# SCH_nixie_clock_2022-01-09.net
KiCad netlist of a schematic drawn in EasyEDA
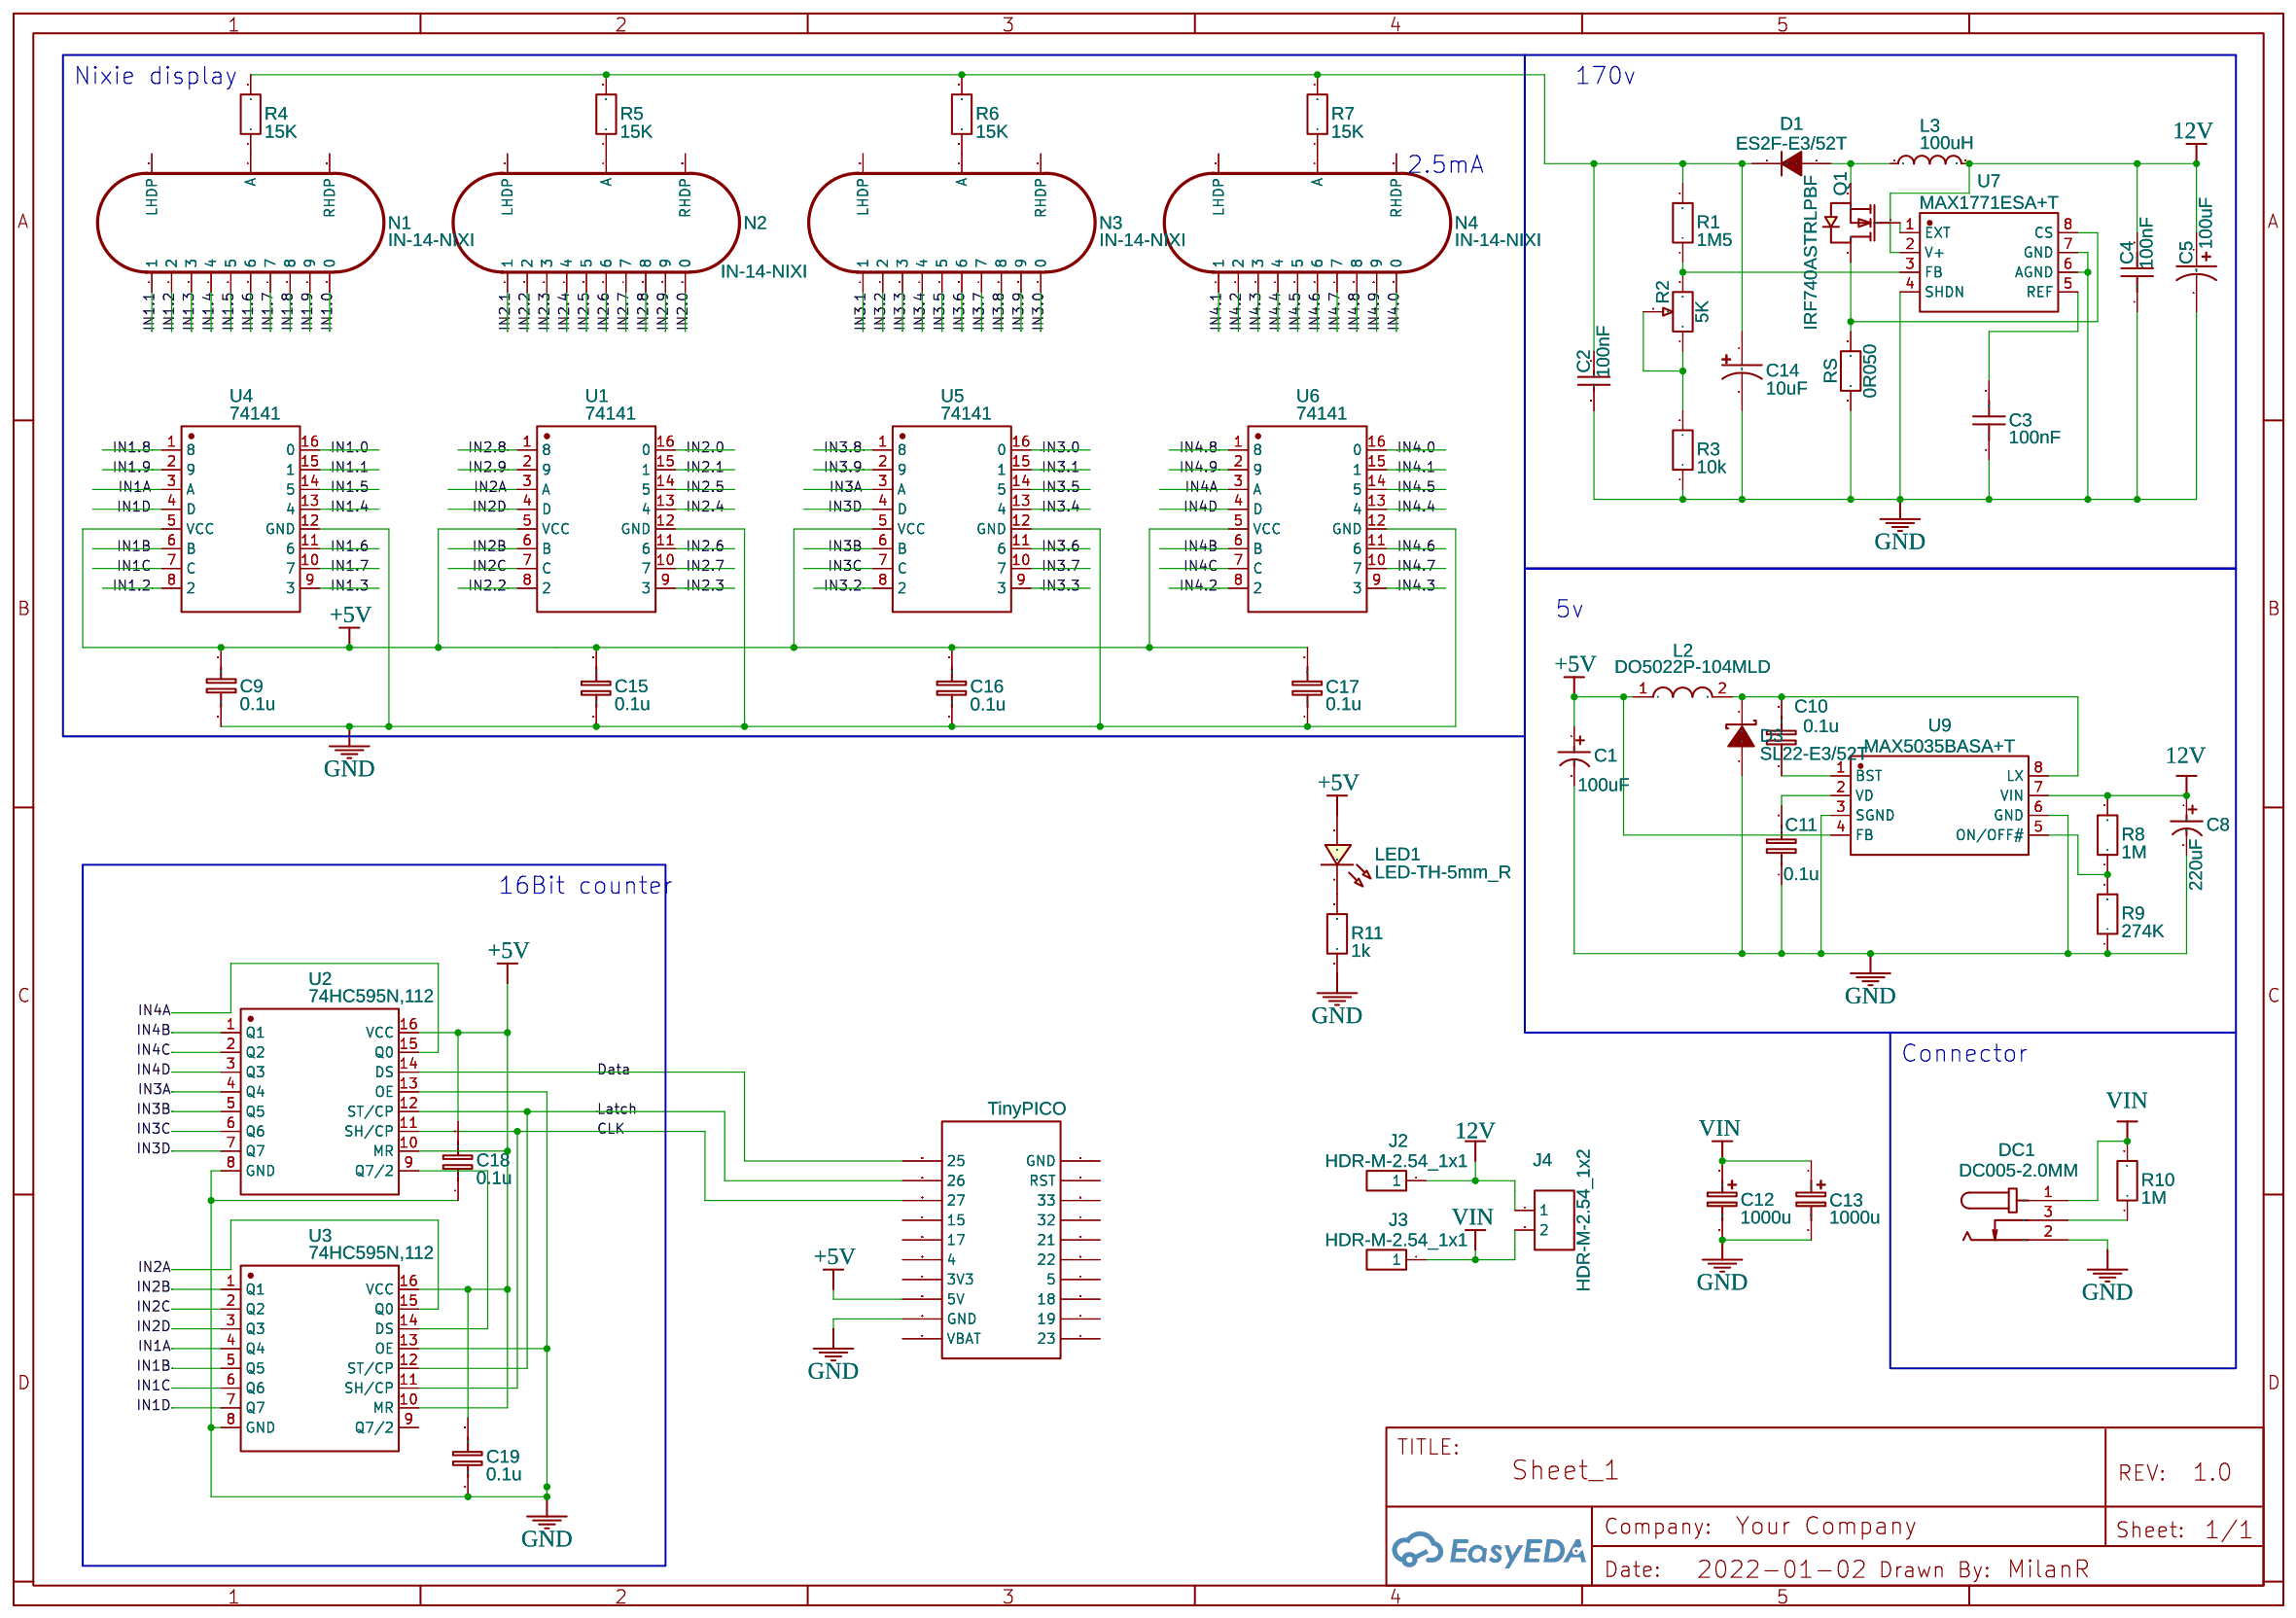
[diagram p0: Sheet_1]
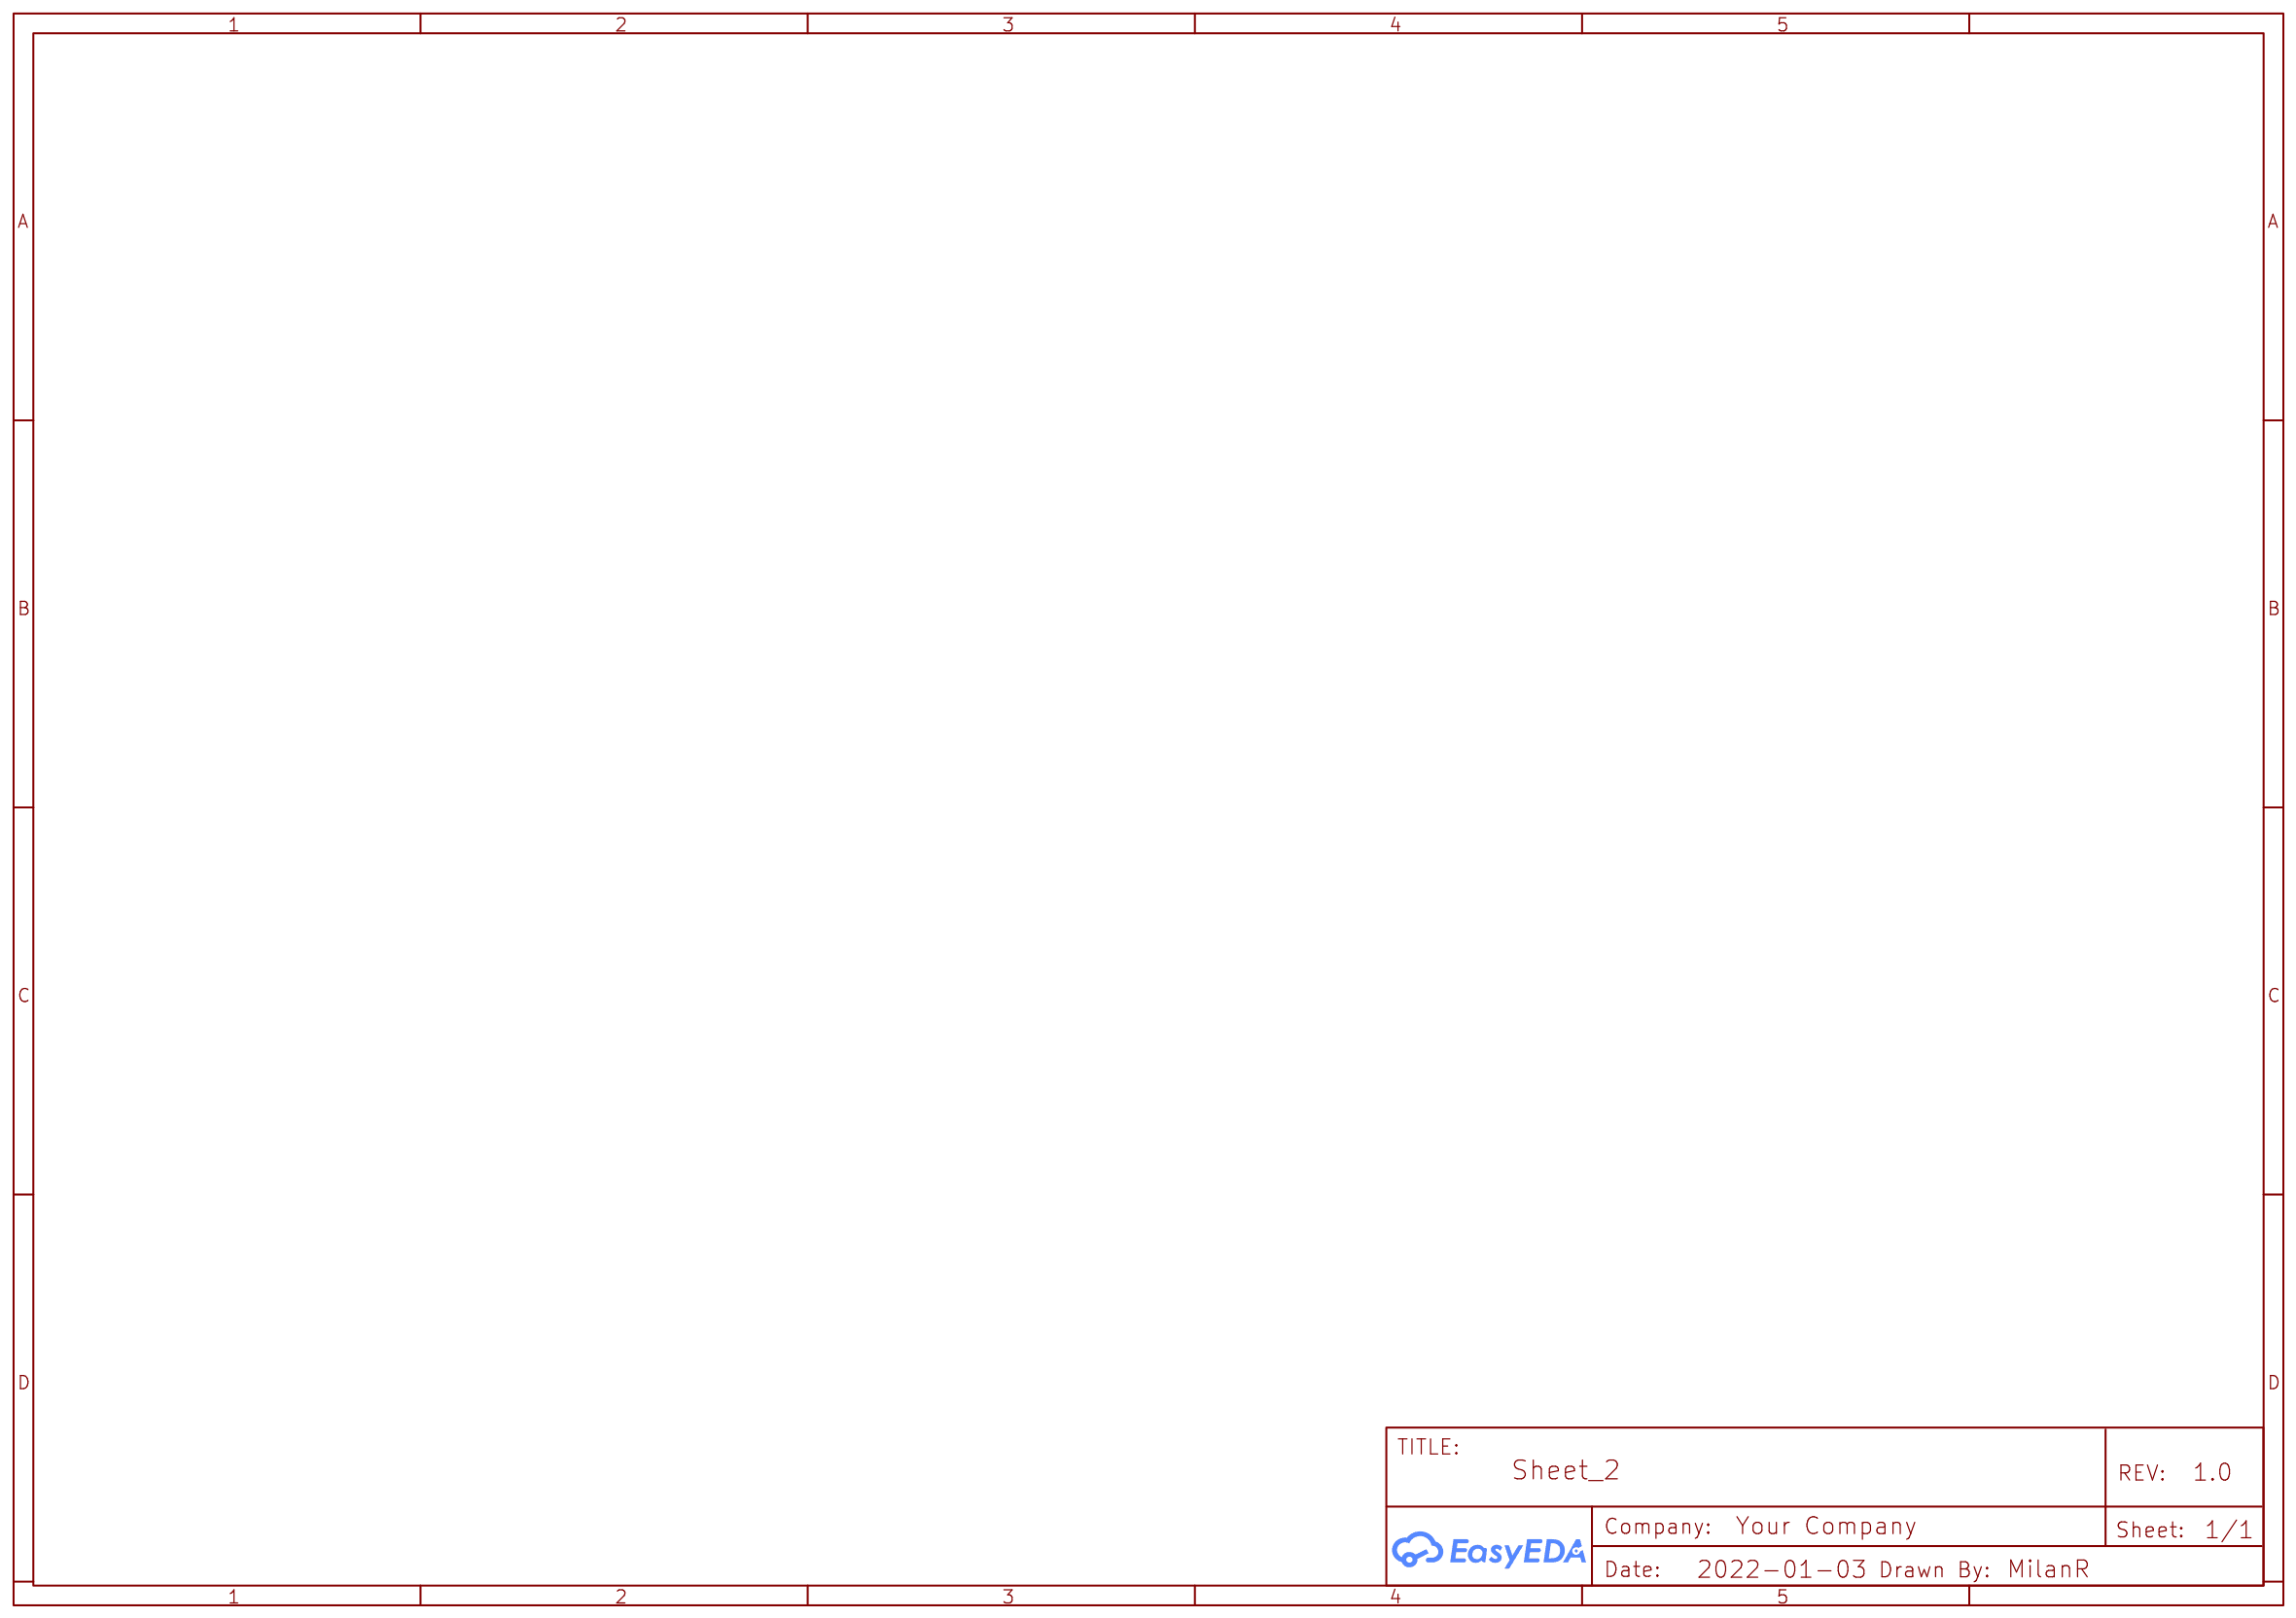
[diagram p1: Sheet_2]

(export (version "E")
  (design (tool "Eeschema 10.0.6"))
  (components
    (comp (ref "C1")
      (value "100uF")
      (fields
        (field (name "BOM_Manufacturer Part") "25YXJ100M5X11")
        (field (name "BOM_Supplier Part") "C108360")
      )
      (libsource (lib "") (part "25YXJ100M5X11"))
    )
    (comp (ref "C2")
      (value "100nF")
      (fields
        (field (name "BOM_Manufacturer Part") "C3225X7R2E104KT020U")
        (field (name "BOM_Supplier Part") "C76688")
      )
      (libsource (lib "") (part "C3225X7R2E104KT020U"))
    )
    (comp (ref "C3")
      (value "100nF")
      (fields
        (field (name "BOM_Manufacturer Part") "0805B104J500")
        (field (name "BOM_Supplier Part") "C116832")
      )
      (libsource (lib "") (part "0805B104J500"))
    )
    (comp (ref "C4")
      (value "100nF")
      (fields
        (field (name "BOM_Manufacturer Part") "0805B104J500")
        (field (name "BOM_Supplier Part") "C116832")
      )
      (libsource (lib "") (part "0805B104J500"))
    )
    (comp (ref "C5")
      (value "100uF")
      (fields
        (field (name "BOM_Manufacturer Part") "TPSD107K020R0100")
        (field (name "BOM_Supplier Part") "C444810")
      )
      (libsource (lib "") (part "TPSD107K020R0100"))
    )
    (comp (ref "C8")
      (value "220uF")
      (fields
        (field (name "BOM_Manufacturer Part") "25YXJ220M6.3X11")
        (field (name "BOM_Supplier Part") "C88729")
      )
      (libsource (lib "") (part "25YXJ220M6.3X11"))
    )
    (comp (ref "C9") (value "0.1u") (libsource (lib "") (part "C_0805_EU_2")))
    (comp (ref "C10") (value "0.1u") (libsource (lib "") (part "C_0805_EU")))
    (comp (ref "C11") (value "0.1u") (libsource (lib "") (part "C_0805_EU")))
    (comp (ref "C12") (value "1000u") (libsource (lib "") (part "CE_TH_D10.0×F5.0_EU")))
    (comp (ref "C13") (value "1000u") (libsource (lib "") (part "CE_TH_D10.0×F5.0_EU")))
    (comp (ref "C14")
      (value "10uF")
      (fields
        (field (name "BOM_Manufacturer Part") "ECA2EHG100")
        (field (name "BOM_Supplier Part") "C178409")
      )
      (libsource (lib "") (part "ECA2EHG100"))
    )
    (comp (ref "C15") (value "0.1u") (libsource (lib "") (part "C_0805_EU_1")))
    (comp (ref "C16") (value "0.1u") (libsource (lib "") (part "C_0805_EU_1")))
    (comp (ref "C17") (value "0.1u") (libsource (lib "") (part "C_0805_EU")))
    (comp (ref "C18") (value "0.1u") (libsource (lib "") (part "C_0805_EU_1")))
    (comp (ref "C19") (value "0.1u") (libsource (lib "") (part "C_0805_EU_3")))
    (comp (ref "D1")
      (value "ES2F-E3/52T")
      (fields (field (name "BOM_Supplier Part") "C145321"))
      (libsource (lib "") (part "ES2F-E3/52T"))
    )
    (comp (ref "D3")
      (value "SL22-E3/52T")
      (fields (field (name "BOM_Supplier Part") "C142616"))
      (libsource (lib "") (part "SL22-E3/52T"))
    )
    (comp (ref "DC1")
      (value "DC005-2.0MM")
      (fields (field (name "BOM_Supplier Part") "C111567"))
      (libsource (lib "") (part "DC005-2.0MM"))
    )
    (comp (ref "J2")
      (value "HDR-M-2.54_1x1")
      (fields (field (name "BOM_Supplier Part") "C81276"))
      (libsource (lib "") (part "HDR-M-2.54_1x1"))
    )
    (comp (ref "J3")
      (value "HDR-M-2.54_1x1")
      (fields (field (name "BOM_Supplier Part") "C81276"))
      (libsource (lib "") (part "HDR-M-2.54_1x1"))
    )
    (comp (ref "J4")
      (value "HDR-M-2.54_1x2")
      (fields (field (name "BOM_Supplier Part") "C124375"))
      (libsource (lib "") (part "HDR-M-2.54_1x2"))
    )
    (comp (ref "L2") (value "DO5022P-104MLD") (libsource (lib "") (part "DO5022P-104MLD")))
    (comp (ref "L3")
      (value "100uH")
      (fields
        (field (name "BOM_Manufacturer Part") "IHLP6767GZER101M11")
        (field (name "BOM_Supplier Part") "541-1294-1-ND")
      )
      (libsource (lib "") (part "IHLP6767GZER101M11"))
    )
    (comp (ref "LED1")
      (value "LED-TH-5mm_R")
      (fields
        (field (name "BOM_Manufacturer Part") "333-2SURD/S530-A3")
        (field (name "BOM_Supplier Part") "C87271")
      )
      (libsource (lib "") (part "LED-TH-5mm_R"))
    )
    (comp (ref "N1") (value "IN-14-NIXI") (libsource (lib "") (part "IN-14-NIXI")))
    (comp (ref "N2") (value "IN-14-NIXI") (libsource (lib "") (part "IN-14-NIXI")))
    (comp (ref "N3") (value "IN-14-NIXI") (libsource (lib "") (part "IN-14-NIXI")))
    (comp (ref "N4") (value "IN-14-NIXI") (libsource (lib "") (part "IN-14-NIXI")))
    (comp (ref "NO") (value "TinyPICO") (libsource (lib "") (part "TinyPICO")))
    (comp (ref "Q1")
      (value "IRF740ASTRLPBF")
      (fields (field (name "BOM_Supplier Part") "C467558"))
      (libsource (lib "") (part "IRF740ASTRLPBF"))
    )
    (comp (ref "R1") (value "1M5") (libsource (lib "") (part "R_1206_EU")))
    (comp (ref "R2")
      (value "5K")
      (fields (field (name "BOM_Supplier Part") "C132878"))
      (libsource (lib "") (part "ST-4EA 5K ohm (502)"))
    )
    (comp (ref "R3") (value "10k") (libsource (lib "") (part "R_1206_EU")))
    (comp (ref "R4") (value "15K") (libsource (lib "") (part "R_AXIAL-0.3_EU")))
    (comp (ref "R5") (value "15K") (libsource (lib "") (part "R_AXIAL-0.3_EU")))
    (comp (ref "R6") (value "15K") (libsource (lib "") (part "R_AXIAL-0.3_EU")))
    (comp (ref "R7") (value "15K") (libsource (lib "") (part "R_AXIAL-0.3_EU")))
    (comp (ref "R8") (value "1M") (libsource (lib "") (part "R_0805_EU")))
    (comp (ref "R9") (value "274K") (libsource (lib "") (part "R_0805_EU")))
    (comp (ref "R10") (value "1M") (libsource (lib "") (part "R_0805_EU")))
    (comp (ref "R11") (value "1k") (libsource (lib "") (part "R_0805_EU")))
    (comp (ref "RS") (value "0R050") (libsource (lib "") (part "R_0805_EU_1")))
    (comp (ref "U1") (value "74141") (libsource (lib "") (part "74141")))
    (comp (ref "U2") (value "74HC595N,112") (libsource (lib "") (part "74HC595N,112")))
    (comp (ref "U3") (value "74HC595N,112") (libsource (lib "") (part "74HC595N,112")))
    (comp (ref "U4") (value "74141") (libsource (lib "") (part "74141")))
    (comp (ref "U5") (value "74141") (libsource (lib "") (part "74141")))
    (comp (ref "U6") (value "74141") (libsource (lib "") (part "74141")))
    (comp (ref "U7")
      (value "MAX1771ESA+T")
      (fields (field (name "BOM_Supplier Part") "C407903"))
      (libsource (lib "") (part "MAX1771ESA+T"))
    )
    (comp (ref "U9")
      (value "MAX5035BASA+T")
      (fields (field (name "BOM_Supplier Part") "C39144"))
      (libsource (lib "") (part "MAX5035BASA+T"))
    )
  )
  (nets
    (net (code "1") (name "+5V") (class "Default")
      (node (ref "C1") (pin "1") (pinfunction "1_1") (pintype "input"))
      (node (ref "C15") (pin "2") (pinfunction "2_2") (pintype "unspecified"))
      (node (ref "C16") (pin "2") (pinfunction "2_2") (pintype "unspecified"))
      (node (ref "C17") (pin "2") (pinfunction "2_2") (pintype "unspecified"))
      (node (ref "C18") (pin "2") (pinfunction "2_2") (pintype "unspecified"))
      (node (ref "C19") (pin "2") (pinfunction "2_2") (pintype "unspecified"))
      (node (ref "C9") (pin "1") (pinfunction "1_1") (pintype "unspecified"))
      (node (ref "L2") (pin "1") (pinfunction "1_1") (pintype "bidirectional"))
      (node (ref "LED1") (pin "1") (pinfunction "1_1") (pintype "unspecified"))
      (node (ref "NO") (pin "13") (pinfunction "5V_13") (pintype "unspecified"))
      (node (ref "U1") (pin "5") (pinfunction "VCC_5") (pintype "unspecified"))
      (node (ref "U2") (pin "10") (pinfunction "MR_10") (pintype "unspecified"))
      (node (ref "U2") (pin "16") (pinfunction "VCC_16") (pintype "unspecified"))
      (node (ref "U3") (pin "10") (pinfunction "MR_10") (pintype "unspecified"))
      (node (ref "U3") (pin "16") (pinfunction "VCC_16") (pintype "unspecified"))
      (node (ref "U4") (pin "5") (pinfunction "VCC_5") (pintype "unspecified"))
      (node (ref "U5") (pin "5") (pinfunction "VCC_5") (pintype "unspecified"))
      (node (ref "U6") (pin "5") (pinfunction "VCC_5") (pintype "unspecified"))
      (node (ref "U9") (pin "4") (pinfunction "FB_4") (pintype "unspecified"))
    )
    (net (code "2") (name "12V") (class "Default")
      (node (ref "C4") (pin "2") (pinfunction "2_2") (pintype "unspecified"))
      (node (ref "C5") (pin "1") (pinfunction "1_1") (pintype "unspecified"))
      (node (ref "C8") (pin "1") (pinfunction "1_1") (pintype "input"))
      (node (ref "J2") (pin "1") (pinfunction "1_1") (pintype "input"))
      (node (ref "J4") (pin "1") (pinfunction "1_1") (pintype "unspecified"))
      (node (ref "L3") (pin "2") (pinfunction "2_2") (pintype "unspecified"))
      (node (ref "R8") (pin "2") (pinfunction "2_2") (pintype "unspecified"))
      (node (ref "U7") (pin "2") (pinfunction "V+_2") (pintype "unspecified"))
      (node (ref "U9") (pin "7") (pinfunction "VIN_7") (pintype "unspecified"))
    )
    (net (code "3") (name "CLK") (class "Default")
      (node (ref "NO") (pin "18") (pinfunction "27_18") (pintype "bidirectional"))
      (node (ref "U2") (pin "11") (pinfunction "SH/CP_11") (pintype "unspecified"))
      (node (ref "U3") (pin "11") (pinfunction "SH/CP_11") (pintype "unspecified"))
    )
    (net (code "4") (name "Data") (class "Default")
      (node (ref "NO") (pin "20") (pinfunction "25_20") (pintype "bidirectional"))
      (node (ref "U2") (pin "14") (pinfunction "DS_14") (pintype "unspecified"))
    )
    (net (code "5") (name "GND") (class "Default")
      (node (ref "C1") (pin "2") (pinfunction "2_2") (pintype "input"))
      (node (ref "C11") (pin "1") (pinfunction "1_1") (pintype "unspecified"))
      (node (ref "C12") (pin "2") (pinfunction "2_2") (pintype "unspecified"))
      (node (ref "C13") (pin "2") (pinfunction "2_2") (pintype "unspecified"))
      (node (ref "C14") (pin "2") (pinfunction "2_2") (pintype "unspecified"))
      (node (ref "C15") (pin "1") (pinfunction "1_1") (pintype "unspecified"))
      (node (ref "C16") (pin "1") (pinfunction "1_1") (pintype "unspecified"))
      (node (ref "C17") (pin "1") (pinfunction "1_1") (pintype "unspecified"))
      (node (ref "C18") (pin "1") (pinfunction "1_1") (pintype "unspecified"))
      (node (ref "C19") (pin "1") (pinfunction "1_1") (pintype "unspecified"))
      (node (ref "C2") (pin "1") (pinfunction "1_1") (pintype "input"))
      (node (ref "C3") (pin "1") (pinfunction "1_1") (pintype "unspecified"))
      (node (ref "C4") (pin "1") (pinfunction "1_1") (pintype "unspecified"))
      (node (ref "C5") (pin "2") (pinfunction "2_2") (pintype "unspecified"))
      (node (ref "C8") (pin "2") (pinfunction "2_2") (pintype "input"))
      (node (ref "C9") (pin "2") (pinfunction "2_2") (pintype "unspecified"))
      (node (ref "D3") (pin "2") (pinfunction "A_2") (pintype "unspecified"))
      (node (ref "DC1") (pin "2") (pinfunction "2_2") (pintype "unspecified"))
      (node (ref "NO") (pin "12") (pinfunction "GND_12") (pintype "unspecified"))
      (node (ref "R11") (pin "1") (pinfunction "1_1") (pintype "unspecified"))
      (node (ref "R3") (pin "1") (pinfunction "1_1") (pintype "unspecified"))
      (node (ref "R9") (pin "1") (pinfunction "1_1") (pintype "unspecified"))
      (node (ref "RS") (pin "1") (pinfunction "1_1") (pintype "unspecified"))
      (node (ref "U1") (pin "12") (pinfunction "GND_12") (pintype "unspecified"))
      (node (ref "U2") (pin "13") (pinfunction "OE_13") (pintype "unspecified"))
      (node (ref "U2") (pin "8") (pinfunction "GND_8") (pintype "unspecified"))
      (node (ref "U3") (pin "13") (pinfunction "OE_13") (pintype "unspecified"))
      (node (ref "U3") (pin "8") (pinfunction "GND_8") (pintype "unspecified"))
      (node (ref "U4") (pin "12") (pinfunction "GND_12") (pintype "unspecified"))
      (node (ref "U5") (pin "12") (pinfunction "GND_12") (pintype "unspecified"))
      (node (ref "U6") (pin "12") (pinfunction "GND_12") (pintype "unspecified"))
      (node (ref "U7") (pin "4") (pinfunction "SHDN_4") (pintype "unspecified"))
      (node (ref "U7") (pin "6") (pinfunction "AGND_6") (pintype "unspecified"))
      (node (ref "U7") (pin "7") (pinfunction "GND_7") (pintype "unspecified"))
      (node (ref "U9") (pin "3") (pinfunction "SGND_3") (pintype "unspecified"))
      (node (ref "U9") (pin "6") (pinfunction "GND_6") (pintype "unspecified"))
    )
    (net (code "6") (name "IN1.0") (class "Default")
      (node (ref "N1") (pin "0") (pinfunction "0_0") (pintype "bidirectional"))
      (node (ref "U4") (pin "16") (pinfunction "0_16") (pintype "unspecified"))
    )
    (net (code "7") (name "IN1.1") (class "Default")
      (node (ref "N1") (pin "1") (pinfunction "1_1") (pintype "bidirectional"))
      (node (ref "U4") (pin "15") (pinfunction "1_15") (pintype "unspecified"))
    )
    (net (code "8") (name "IN1.2") (class "Default")
      (node (ref "N1") (pin "2") (pinfunction "2_2") (pintype "bidirectional"))
      (node (ref "U4") (pin "8") (pinfunction "2_8") (pintype "unspecified"))
    )
    (net (code "9") (name "IN1.3") (class "Default")
      (node (ref "N1") (pin "3") (pinfunction "3_3") (pintype "bidirectional"))
      (node (ref "U4") (pin "9") (pinfunction "3_9") (pintype "unspecified"))
    )
    (net (code "10") (name "IN1.4") (class "Default")
      (node (ref "N1") (pin "4") (pinfunction "4_4") (pintype "bidirectional"))
      (node (ref "U4") (pin "13") (pinfunction "4_13") (pintype "unspecified"))
    )
    (net (code "11") (name "IN1.5") (class "Default")
      (node (ref "N1") (pin "5") (pinfunction "5_5") (pintype "bidirectional"))
      (node (ref "U4") (pin "14") (pinfunction "5_14") (pintype "unspecified"))
    )
    (net (code "12") (name "IN1.6") (class "Default")
      (node (ref "N1") (pin "6") (pinfunction "6_6") (pintype "bidirectional"))
      (node (ref "U4") (pin "11") (pinfunction "6_11") (pintype "unspecified"))
    )
    (net (code "13") (name "IN1.7") (class "Default")
      (node (ref "N1") (pin "7") (pinfunction "7_7") (pintype "bidirectional"))
      (node (ref "U4") (pin "10") (pinfunction "7_10") (pintype "unspecified"))
    )
    (net (code "14") (name "IN1.8") (class "Default")
      (node (ref "N1") (pin "8") (pinfunction "8_8") (pintype "bidirectional"))
      (node (ref "U4") (pin "1") (pinfunction "8_1") (pintype "unspecified"))
    )
    (net (code "15") (name "IN1.9") (class "Default")
      (node (ref "N1") (pin "9") (pinfunction "9_9") (pintype "bidirectional"))
      (node (ref "U4") (pin "2") (pinfunction "9_2") (pintype "unspecified"))
    )
    (net (code "16") (name "IN1A") (class "Default")
      (node (ref "U3") (pin "4") (pinfunction "Q4_4") (pintype "unspecified"))
      (node (ref "U4") (pin "3") (pinfunction "A_3") (pintype "unspecified"))
    )
    (net (code "17") (name "IN1B") (class "Default")
      (node (ref "U3") (pin "5") (pinfunction "Q5_5") (pintype "unspecified"))
      (node (ref "U4") (pin "6") (pinfunction "B_6") (pintype "unspecified"))
    )
    (net (code "18") (name "IN1C") (class "Default")
      (node (ref "U3") (pin "6") (pinfunction "Q6_6") (pintype "unspecified"))
      (node (ref "U4") (pin "7") (pinfunction "C_7") (pintype "unspecified"))
    )
    (net (code "19") (name "IN1D") (class "Default")
      (node (ref "U3") (pin "7") (pinfunction "Q7_7") (pintype "unspecified"))
      (node (ref "U4") (pin "4") (pinfunction "D_4") (pintype "unspecified"))
    )
    (net (code "20") (name "IN2.0") (class "Default")
      (node (ref "N2") (pin "0") (pinfunction "0_0") (pintype "bidirectional"))
      (node (ref "U1") (pin "16") (pinfunction "0_16") (pintype "unspecified"))
    )
    (net (code "21") (name "IN2.1") (class "Default")
      (node (ref "N2") (pin "1") (pinfunction "1_1") (pintype "bidirectional"))
      (node (ref "U1") (pin "15") (pinfunction "1_15") (pintype "unspecified"))
    )
    (net (code "22") (name "IN2.2") (class "Default")
      (node (ref "N2") (pin "2") (pinfunction "2_2") (pintype "bidirectional"))
      (node (ref "U1") (pin "8") (pinfunction "2_8") (pintype "unspecified"))
    )
    (net (code "23") (name "IN2.3") (class "Default")
      (node (ref "N2") (pin "3") (pinfunction "3_3") (pintype "bidirectional"))
      (node (ref "U1") (pin "9") (pinfunction "3_9") (pintype "unspecified"))
    )
    (net (code "24") (name "IN2.4") (class "Default")
      (node (ref "N2") (pin "4") (pinfunction "4_4") (pintype "bidirectional"))
      (node (ref "U1") (pin "13") (pinfunction "4_13") (pintype "unspecified"))
    )
    (net (code "25") (name "IN2.5") (class "Default")
      (node (ref "N2") (pin "5") (pinfunction "5_5") (pintype "bidirectional"))
      (node (ref "U1") (pin "14") (pinfunction "5_14") (pintype "unspecified"))
    )
    (net (code "26") (name "IN2.6") (class "Default")
      (node (ref "N2") (pin "6") (pinfunction "6_6") (pintype "bidirectional"))
      (node (ref "U1") (pin "11") (pinfunction "6_11") (pintype "unspecified"))
    )
    (net (code "27") (name "IN2.7") (class "Default")
      (node (ref "N2") (pin "7") (pinfunction "7_7") (pintype "bidirectional"))
      (node (ref "U1") (pin "10") (pinfunction "7_10") (pintype "unspecified"))
    )
    (net (code "28") (name "IN2.8") (class "Default")
      (node (ref "N2") (pin "8") (pinfunction "8_8") (pintype "bidirectional"))
      (node (ref "U1") (pin "1") (pinfunction "8_1") (pintype "unspecified"))
    )
    (net (code "29") (name "IN2.9") (class "Default")
      (node (ref "N2") (pin "9") (pinfunction "9_9") (pintype "bidirectional"))
      (node (ref "U1") (pin "2") (pinfunction "9_2") (pintype "unspecified"))
    )
    (net (code "30") (name "IN2A") (class "Default")
      (node (ref "U1") (pin "3") (pinfunction "A_3") (pintype "unspecified"))
      (node (ref "U3") (pin "15") (pinfunction "Q0_15") (pintype "unspecified"))
    )
    (net (code "31") (name "IN2B") (class "Default")
      (node (ref "U1") (pin "6") (pinfunction "B_6") (pintype "unspecified"))
      (node (ref "U3") (pin "1") (pinfunction "Q1_1") (pintype "unspecified"))
    )
    (net (code "32") (name "IN2C") (class "Default")
      (node (ref "U1") (pin "7") (pinfunction "C_7") (pintype "unspecified"))
      (node (ref "U3") (pin "2") (pinfunction "Q2_2") (pintype "unspecified"))
    )
    (net (code "33") (name "IN2D") (class "Default")
      (node (ref "U1") (pin "4") (pinfunction "D_4") (pintype "unspecified"))
      (node (ref "U3") (pin "3") (pinfunction "Q3_3") (pintype "unspecified"))
    )
    (net (code "34") (name "IN3.0") (class "Default")
      (node (ref "N3") (pin "0") (pinfunction "0_0") (pintype "bidirectional"))
      (node (ref "U5") (pin "16") (pinfunction "0_16") (pintype "unspecified"))
    )
    (net (code "35") (name "IN3.1") (class "Default")
      (node (ref "N3") (pin "1") (pinfunction "1_1") (pintype "bidirectional"))
      (node (ref "U5") (pin "15") (pinfunction "1_15") (pintype "unspecified"))
    )
    (net (code "36") (name "IN3.2") (class "Default")
      (node (ref "N3") (pin "2") (pinfunction "2_2") (pintype "bidirectional"))
      (node (ref "U5") (pin "8") (pinfunction "2_8") (pintype "unspecified"))
    )
    (net (code "37") (name "IN3.3") (class "Default")
      (node (ref "N3") (pin "3") (pinfunction "3_3") (pintype "bidirectional"))
      (node (ref "U5") (pin "9") (pinfunction "3_9") (pintype "unspecified"))
    )
    (net (code "38") (name "IN3.4") (class "Default")
      (node (ref "N3") (pin "4") (pinfunction "4_4") (pintype "bidirectional"))
      (node (ref "U5") (pin "13") (pinfunction "4_13") (pintype "unspecified"))
    )
    (net (code "39") (name "IN3.5") (class "Default")
      (node (ref "N3") (pin "5") (pinfunction "5_5") (pintype "bidirectional"))
      (node (ref "U5") (pin "14") (pinfunction "5_14") (pintype "unspecified"))
    )
    (net (code "40") (name "IN3.6") (class "Default")
      (node (ref "N3") (pin "6") (pinfunction "6_6") (pintype "bidirectional"))
      (node (ref "U5") (pin "11") (pinfunction "6_11") (pintype "unspecified"))
    )
    (net (code "41") (name "IN3.7") (class "Default")
      (node (ref "N3") (pin "7") (pinfunction "7_7") (pintype "bidirectional"))
      (node (ref "U5") (pin "10") (pinfunction "7_10") (pintype "unspecified"))
    )
    (net (code "42") (name "IN3.8") (class "Default")
      (node (ref "N3") (pin "8") (pinfunction "8_8") (pintype "bidirectional"))
      (node (ref "U5") (pin "1") (pinfunction "8_1") (pintype "unspecified"))
    )
    (net (code "43") (name "IN3.9") (class "Default")
      (node (ref "N3") (pin "9") (pinfunction "9_9") (pintype "bidirectional"))
      (node (ref "U5") (pin "2") (pinfunction "9_2") (pintype "unspecified"))
    )
    (net (code "44") (name "IN3A") (class "Default")
      (node (ref "U2") (pin "4") (pinfunction "Q4_4") (pintype "unspecified"))
      (node (ref "U5") (pin "3") (pinfunction "A_3") (pintype "unspecified"))
    )
    (net (code "45") (name "IN3B") (class "Default")
      (node (ref "U2") (pin "5") (pinfunction "Q5_5") (pintype "unspecified"))
      (node (ref "U5") (pin "6") (pinfunction "B_6") (pintype "unspecified"))
    )
    (net (code "46") (name "IN3C") (class "Default")
      (node (ref "U2") (pin "6") (pinfunction "Q6_6") (pintype "unspecified"))
      (node (ref "U5") (pin "7") (pinfunction "C_7") (pintype "unspecified"))
    )
    (net (code "47") (name "IN3D") (class "Default")
      (node (ref "U2") (pin "7") (pinfunction "Q7_7") (pintype "unspecified"))
      (node (ref "U5") (pin "4") (pinfunction "D_4") (pintype "unspecified"))
    )
    (net (code "48") (name "IN4.0") (class "Default")
      (node (ref "N4") (pin "0") (pinfunction "0_0") (pintype "bidirectional"))
      (node (ref "U6") (pin "16") (pinfunction "0_16") (pintype "unspecified"))
    )
    (net (code "49") (name "IN4.1") (class "Default")
      (node (ref "N4") (pin "1") (pinfunction "1_1") (pintype "bidirectional"))
      (node (ref "U6") (pin "15") (pinfunction "1_15") (pintype "unspecified"))
    )
    (net (code "50") (name "IN4.2") (class "Default")
      (node (ref "N4") (pin "2") (pinfunction "2_2") (pintype "bidirectional"))
      (node (ref "U6") (pin "8") (pinfunction "2_8") (pintype "unspecified"))
    )
    (net (code "51") (name "IN4.3") (class "Default")
      (node (ref "N4") (pin "3") (pinfunction "3_3") (pintype "bidirectional"))
      (node (ref "U6") (pin "9") (pinfunction "3_9") (pintype "unspecified"))
    )
    (net (code "52") (name "IN4.4") (class "Default")
      (node (ref "N4") (pin "4") (pinfunction "4_4") (pintype "bidirectional"))
      (node (ref "U6") (pin "13") (pinfunction "4_13") (pintype "unspecified"))
    )
    (net (code "53") (name "IN4.5") (class "Default")
      (node (ref "N4") (pin "5") (pinfunction "5_5") (pintype "bidirectional"))
      (node (ref "U6") (pin "14") (pinfunction "5_14") (pintype "unspecified"))
    )
    (net (code "54") (name "IN4.6") (class "Default")
      (node (ref "N4") (pin "6") (pinfunction "6_6") (pintype "bidirectional"))
      (node (ref "U6") (pin "11") (pinfunction "6_11") (pintype "unspecified"))
    )
    (net (code "55") (name "IN4.7") (class "Default")
      (node (ref "N4") (pin "7") (pinfunction "7_7") (pintype "bidirectional"))
      (node (ref "U6") (pin "10") (pinfunction "7_10") (pintype "unspecified"))
    )
    (net (code "56") (name "IN4.8") (class "Default")
      (node (ref "N4") (pin "8") (pinfunction "8_8") (pintype "bidirectional"))
      (node (ref "U6") (pin "1") (pinfunction "8_1") (pintype "unspecified"))
    )
    (net (code "57") (name "IN4.9") (class "Default")
      (node (ref "N4") (pin "9") (pinfunction "9_9") (pintype "bidirectional"))
      (node (ref "U6") (pin "2") (pinfunction "9_2") (pintype "unspecified"))
    )
    (net (code "58") (name "IN4A") (class "Default")
      (node (ref "U2") (pin "15") (pinfunction "Q0_15") (pintype "unspecified"))
      (node (ref "U6") (pin "3") (pinfunction "A_3") (pintype "unspecified"))
    )
    (net (code "59") (name "IN4B") (class "Default")
      (node (ref "U2") (pin "1") (pinfunction "Q1_1") (pintype "unspecified"))
      (node (ref "U6") (pin "6") (pinfunction "B_6") (pintype "unspecified"))
    )
    (net (code "60") (name "IN4C") (class "Default")
      (node (ref "U2") (pin "2") (pinfunction "Q2_2") (pintype "unspecified"))
      (node (ref "U6") (pin "7") (pinfunction "C_7") (pintype "unspecified"))
    )
    (net (code "61") (name "IN4D") (class "Default")
      (node (ref "U2") (pin "3") (pinfunction "Q3_3") (pintype "unspecified"))
      (node (ref "U6") (pin "4") (pinfunction "D_4") (pintype "unspecified"))
    )
    (net (code "62") (name "Latch") (class "Default")
      (node (ref "NO") (pin "19") (pinfunction "26_19") (pintype "bidirectional"))
      (node (ref "U2") (pin "12") (pinfunction "ST/CP_12") (pintype "unspecified"))
      (node (ref "U3") (pin "12") (pinfunction "ST/CP_12") (pintype "unspecified"))
    )
    (net (code "63") (name "Net-(D1-A)") (class "Default")
      (node (ref "D1") (pin "2") (pinfunction "A_2") (pintype "unspecified"))
      (node (ref "L3") (pin "1") (pinfunction "1_1") (pintype "unspecified"))
      (node (ref "Q1") (pin "3") (pinfunction "S_3") (pintype "unspecified"))
    )
    (net (code "64") (name "Net-(D1-K)") (class "Default")
      (node (ref "C14") (pin "1") (pinfunction "1_1") (pintype "unspecified"))
      (node (ref "C2") (pin "2") (pinfunction "2_2") (pintype "input"))
      (node (ref "D1") (pin "1") (pinfunction "K_1") (pintype "unspecified"))
      (node (ref "R1") (pin "2") (pinfunction "2_2") (pintype "unspecified"))
      (node (ref "R4") (pin "2") (pinfunction "2_2") (pintype "unspecified"))
      (node (ref "R5") (pin "2") (pinfunction "2_2") (pintype "unspecified"))
      (node (ref "R6") (pin "2") (pinfunction "2_2") (pintype "unspecified"))
      (node (ref "R7") (pin "2") (pinfunction "2_2") (pintype "unspecified"))
    )
    (net (code "65") (name "Net-(D3-K)") (class "Default")
      (node (ref "C10") (pin "2") (pinfunction "2_2") (pintype "unspecified"))
      (node (ref "D3") (pin "1") (pinfunction "K_1") (pintype "unspecified"))
      (node (ref "L2") (pin "2") (pinfunction "2_2") (pintype "bidirectional"))
      (node (ref "U9") (pin "8") (pinfunction "LX_8") (pintype "unspecified"))
    )
    (net (code "66") (name "Net-(DC1-Pad3)") (class "Default")
      (node (ref "DC1") (pin "3") (pinfunction "3_3") (pintype "unspecified"))
      (node (ref "R10") (pin "1") (pinfunction "1_1") (pintype "unspecified"))
    )
    (net (code "67") (name "Net-(LED1-Pad2)") (class "Default")
      (node (ref "LED1") (pin "2") (pinfunction "2_2") (pintype "unspecified"))
      (node (ref "R11") (pin "2") (pinfunction "2_2") (pintype "unspecified"))
    )
    (net (code "68") (name "Net-(N1-PadA)") (class "Default")
      (node (ref "N1") (pin "A") (pinfunction "A_A") (pintype "bidirectional"))
      (node (ref "R4") (pin "1") (pinfunction "1_1") (pintype "unspecified"))
    )
    (net (code "69") (name "Net-(N2-PadA)") (class "Default")
      (node (ref "N2") (pin "A") (pinfunction "A_A") (pintype "bidirectional"))
      (node (ref "R5") (pin "1") (pinfunction "1_1") (pintype "unspecified"))
    )
    (net (code "70") (name "Net-(N3-PadA)") (class "Default")
      (node (ref "N3") (pin "A") (pinfunction "A_A") (pintype "bidirectional"))
      (node (ref "R6") (pin "1") (pinfunction "1_1") (pintype "unspecified"))
    )
    (net (code "71") (name "Net-(N4-PadA)") (class "Default")
      (node (ref "N4") (pin "A") (pinfunction "A_A") (pintype "bidirectional"))
      (node (ref "R7") (pin "1") (pinfunction "1_1") (pintype "unspecified"))
    )
    (net (code "72") (name "Net-(Q1-D)") (class "Default")
      (node (ref "Q1") (pin "2") (pinfunction "D_2") (pintype "unspecified"))
      (node (ref "RS") (pin "2") (pinfunction "2_2") (pintype "unspecified"))
      (node (ref "U7") (pin "8") (pinfunction "CS_8") (pintype "unspecified"))
    )
    (net (code "73") (name "Net-(Q1-G)") (class "Default")
      (node (ref "Q1") (pin "1") (pinfunction "G_1") (pintype "unspecified"))
      (node (ref "U7") (pin "1") (pinfunction "EXT_1") (pintype "unspecified"))
    )
    (net (code "74") (name "Net-(R2-Pad1)") (class "Default")
      (node (ref "R2") (pin "1") (pinfunction "1_1") (pintype "input"))
      (node (ref "R2") (pin "2") (pinfunction "2_2") (pintype "input"))
      (node (ref "R3") (pin "2") (pinfunction "2_2") (pintype "unspecified"))
    )
    (net (code "75") (name "Net-(U2-Q7{slash}2)") (class "Default")
      (node (ref "U2") (pin "9") (pinfunction "Q7/2_9") (pintype "unspecified"))
      (node (ref "U3") (pin "14") (pinfunction "DS_14") (pintype "unspecified"))
    )
    (net (code "76") (name "Net-(U7-FB)") (class "Default")
      (node (ref "R1") (pin "1") (pinfunction "1_1") (pintype "unspecified"))
      (node (ref "R2") (pin "3") (pinfunction "3_3") (pintype "input"))
      (node (ref "U7") (pin "3") (pinfunction "FB_3") (pintype "unspecified"))
    )
    (net (code "77") (name "Net-(U7-REF)") (class "Default")
      (node (ref "C3") (pin "2") (pinfunction "2_2") (pintype "unspecified"))
      (node (ref "U7") (pin "5") (pinfunction "REF_5") (pintype "unspecified"))
    )
    (net (code "78") (name "Net-(U9-BST)") (class "Default")
      (node (ref "C10") (pin "1") (pinfunction "1_1") (pintype "unspecified"))
      (node (ref "U9") (pin "1") (pinfunction "BST_1") (pintype "unspecified"))
    )
    (net (code "79") (name "Net-(U9-ON{slash}OFF#)") (class "Default")
      (node (ref "R8") (pin "1") (pinfunction "1_1") (pintype "unspecified"))
      (node (ref "R9") (pin "2") (pinfunction "2_2") (pintype "unspecified"))
      (node (ref "U9") (pin "5") (pinfunction "ON/OFF#_5") (pintype "unspecified"))
    )
    (net (code "80") (name "Net-(U9-VD)") (class "Default")
      (node (ref "C11") (pin "2") (pinfunction "2_2") (pintype "unspecified"))
      (node (ref "U9") (pin "2") (pinfunction "VD_2") (pintype "unspecified"))
    )
    (net (code "81") (name "VIN") (class "Default")
      (node (ref "C12") (pin "1") (pinfunction "1_1") (pintype "unspecified"))
      (node (ref "C13") (pin "1") (pinfunction "1_1") (pintype "unspecified"))
      (node (ref "DC1") (pin "1") (pinfunction "1_1") (pintype "unspecified"))
      (node (ref "J3") (pin "1") (pinfunction "1_1") (pintype "input"))
      (node (ref "J4") (pin "2") (pinfunction "2_2") (pintype "unspecified"))
      (node (ref "R10") (pin "2") (pinfunction "2_2") (pintype "unspecified"))
    )
    (net (code "82") (name "unconnected-(N1-PadLHDP)") (class "Default")
      (node (ref "N1") (pin "LHDP") (pinfunction "LHDP_LHDP") (pintype "bidirectional"))
    )
    (net (code "83") (name "unconnected-(N1-PadRHDP)") (class "Default")
      (node (ref "N1") (pin "RHDP") (pinfunction "RHDP_RHDP") (pintype "bidirectional"))
    )
    (net (code "84") (name "unconnected-(N2-PadLHDP)") (class "Default")
      (node (ref "N2") (pin "LHDP") (pinfunction "LHDP_LHDP") (pintype "bidirectional"))
    )
    (net (code "85") (name "unconnected-(N2-PadRHDP)") (class "Default")
      (node (ref "N2") (pin "RHDP") (pinfunction "RHDP_RHDP") (pintype "bidirectional"))
    )
    (net (code "86") (name "unconnected-(N3-PadLHDP)") (class "Default")
      (node (ref "N3") (pin "LHDP") (pinfunction "LHDP_LHDP") (pintype "bidirectional"))
    )
    (net (code "87") (name "unconnected-(N3-PadRHDP)") (class "Default")
      (node (ref "N3") (pin "RHDP") (pinfunction "RHDP_RHDP") (pintype "bidirectional"))
    )
    (net (code "88") (name "unconnected-(N4-PadLHDP)") (class "Default")
      (node (ref "N4") (pin "LHDP") (pinfunction "LHDP_LHDP") (pintype "bidirectional"))
    )
    (net (code "89") (name "unconnected-(N4-PadRHDP)") (class "Default")
      (node (ref "N4") (pin "RHDP") (pinfunction "RHDP_RHDP") (pintype "bidirectional"))
    )
    (net (code "90") (name "unconnected-(NO-3V3-Pad14)") (class "Default")
      (node (ref "NO") (pin "14") (pinfunction "3V3_14") (pintype "unspecified"))
    )
    (net (code "91") (name "unconnected-(NO-4-Pad15)") (class "Default")
      (node (ref "NO") (pin "15") (pinfunction "4_15") (pintype "bidirectional"))
    )
    (net (code "92") (name "unconnected-(NO-5-Pad4)") (class "Default")
      (node (ref "NO") (pin "4") (pinfunction "5_4") (pintype "unspecified"))
    )
    (net (code "93") (name "unconnected-(NO-15-Pad17)") (class "Default")
      (node (ref "NO") (pin "17") (pinfunction "15_17") (pintype "bidirectional"))
    )
    (net (code "94") (name "unconnected-(NO-17-Pad16)") (class "Default")
      (node (ref "NO") (pin "16") (pinfunction "17_16") (pintype "bidirectional"))
    )
    (net (code "95") (name "unconnected-(NO-18-Pad3)") (class "Default")
      (node (ref "NO") (pin "3") (pinfunction "18_3") (pintype "unspecified"))
    )
    (net (code "96") (name "unconnected-(NO-19-Pad2)") (class "Default")
      (node (ref "NO") (pin "2") (pinfunction "19_2") (pintype "unspecified"))
    )
    (net (code "97") (name "unconnected-(NO-21-Pad6)") (class "Default")
      (node (ref "NO") (pin "6") (pinfunction "21_6") (pintype "unspecified"))
    )
    (net (code "98") (name "unconnected-(NO-22-Pad5)") (class "Default")
      (node (ref "NO") (pin "5") (pinfunction "22_5") (pintype "unspecified"))
    )
    (net (code "99") (name "unconnected-(NO-23-Pad1)") (class "Default")
      (node (ref "NO") (pin "1") (pinfunction "23_1") (pintype "unspecified"))
    )
    (net (code "100") (name "unconnected-(NO-32-Pad7)") (class "Default")
      (node (ref "NO") (pin "7") (pinfunction "32_7") (pintype "unspecified"))
    )
    (net (code "101") (name "unconnected-(NO-33-Pad8)") (class "Default")
      (node (ref "NO") (pin "8") (pinfunction "33_8") (pintype "unspecified"))
    )
    (net (code "102") (name "unconnected-(NO-GND-Pad10)") (class "Default")
      (node (ref "NO") (pin "10") (pinfunction "GND_10") (pintype "unspecified"))
    )
    (net (code "103") (name "unconnected-(NO-RST-Pad9)") (class "Default")
      (node (ref "NO") (pin "9") (pinfunction "RST_9") (pintype "unspecified"))
    )
    (net (code "104") (name "unconnected-(NO-VBAT-Pad11)") (class "Default")
      (node (ref "NO") (pin "11") (pinfunction "VBAT_11") (pintype "unspecified"))
    )
    (net (code "105") (name "unconnected-(U3-Q7{slash}2-Pad9)") (class "Default")
      (node (ref "U3") (pin "9") (pinfunction "Q7/2_9") (pintype "unspecified"))
    )
  )
)
